# simmodule_adapter_v2_0_1_nov2023.net
KiCad netlist of a schematic drawn in EAGLE
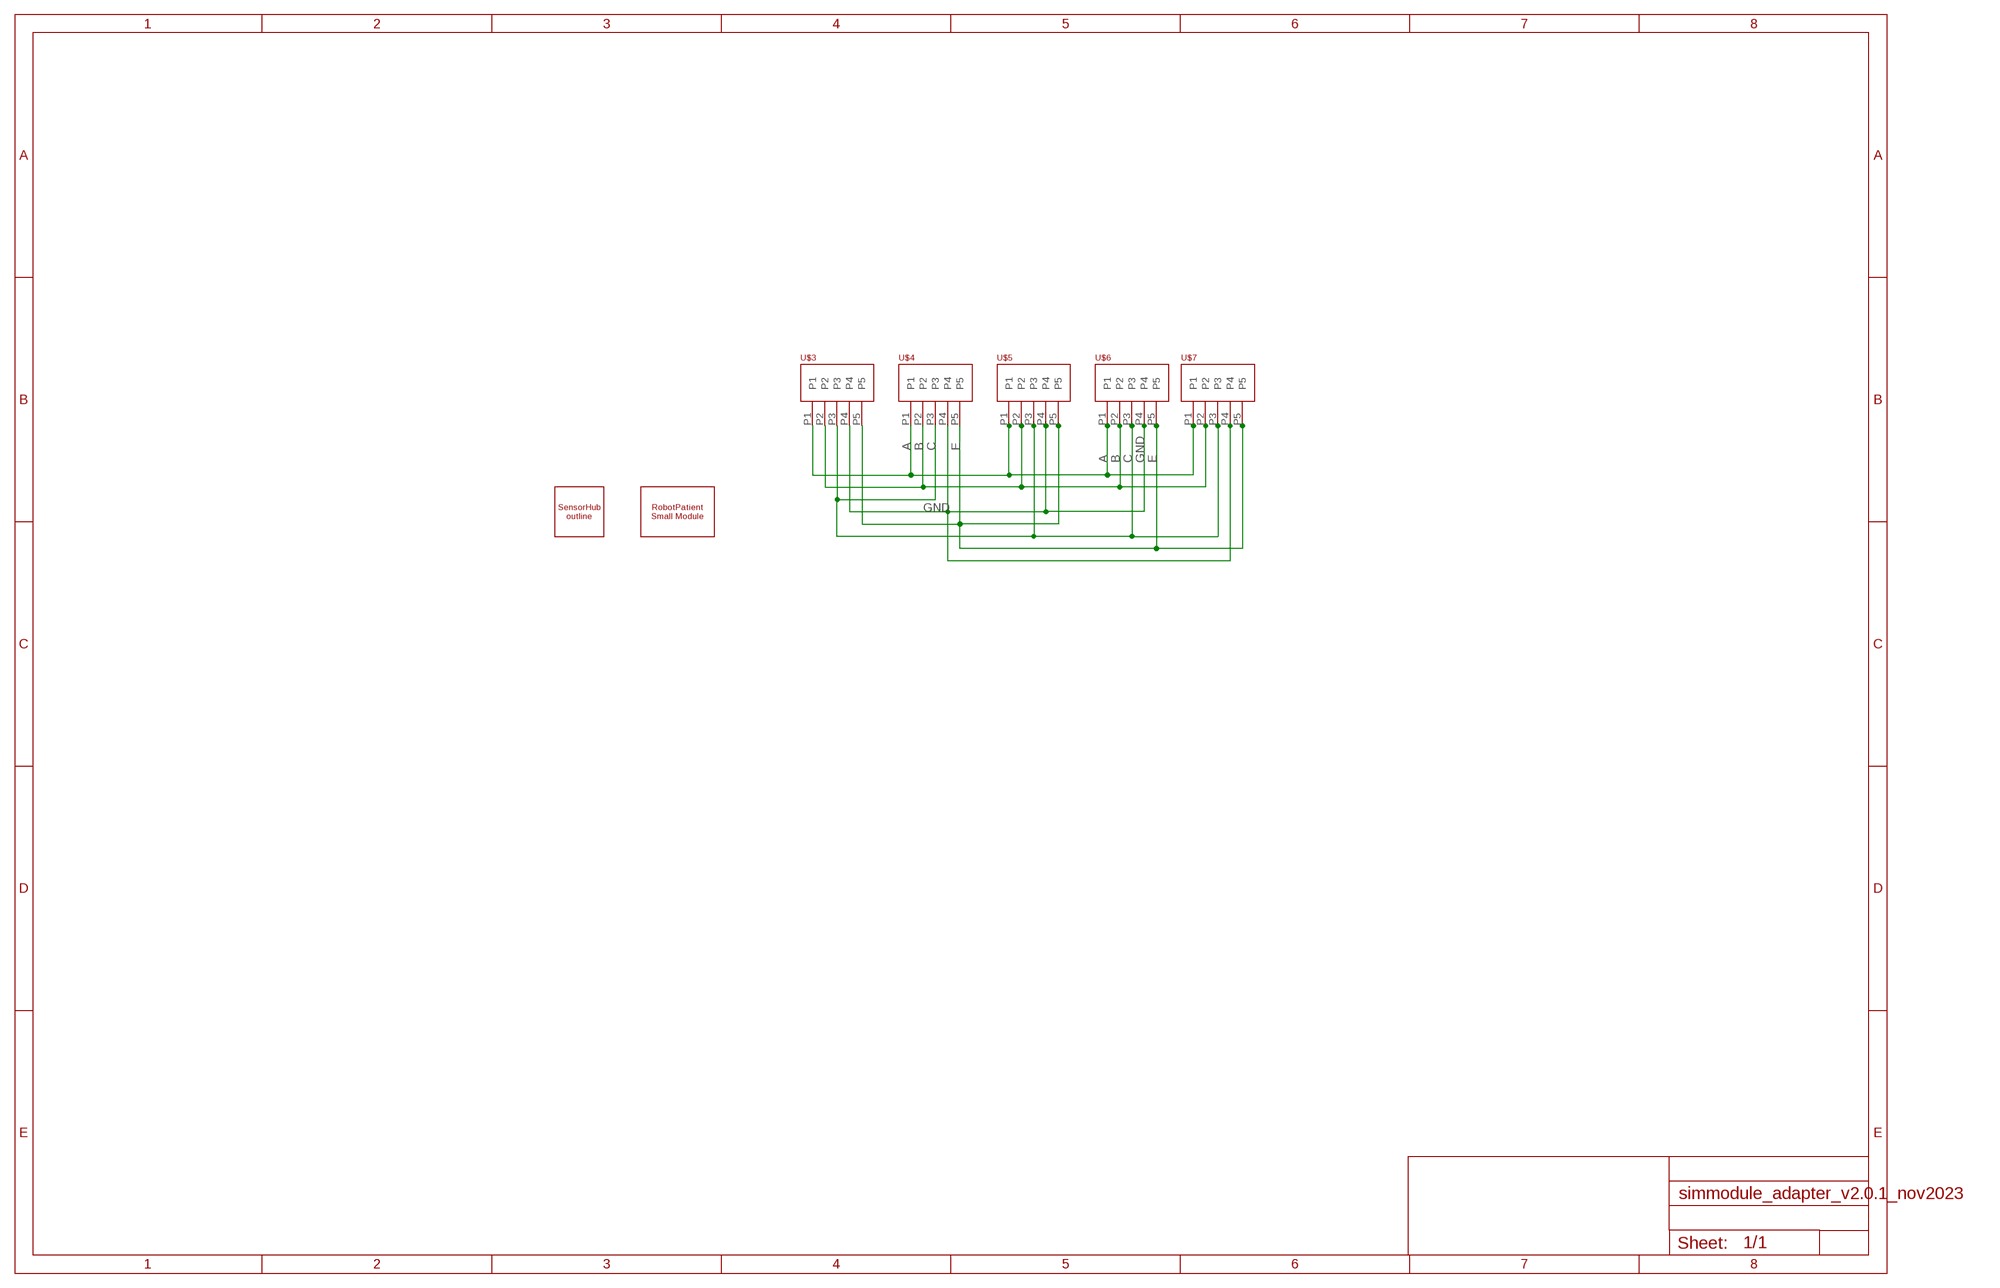
[diagram p0: schematic, sheet 1]

(export (version "E")
  (design (tool "Eeschema 10.0.6"))
  (components
    (comp (ref "U$1")
      (value "SENSORHUB_PROFILEBOARD")
      (footprint "eagle-import:SENSORHUB_OUTLINE")
      (libsource (lib "eagle-import") (part "SENSORHUB_PROFILEBOARD"))
    )
    (comp (ref "U$2")
      (value "ROBOTPATIENT_SMALL_MODULEOUTLINE")
      (footprint "eagle-import:ROBOTPATIENT_SMALL")
      (libsource (lib "eagle-import") (part "ROBOTPATIENT_SMALL_MODULEOUTLINE"))
    )
    (comp (ref "U$3")
      (value "PHOENIX_PTSM_M5_NEUTRAL")
      (footprint "eagle-import:PTSM_M5_TH_NEUTRAL")
      (libsource (lib "eagle-import") (part "PHOENIX_PTSM_M5_NEUTRAL"))
    )
    (comp (ref "U$4")
      (value "PHOENIX_PTSM_M5_NEUTRAL")
      (footprint "eagle-import:PTSM_M5_TH_NEUTRAL")
      (libsource (lib "eagle-import") (part "PHOENIX_PTSM_M5_NEUTRAL"))
    )
    (comp (ref "U$5")
      (value "PHOENIX_PTSM_M5_NEUTRAL")
      (footprint "eagle-import:PTSM_M5_TH_NEUTRAL")
      (libsource (lib "eagle-import") (part "PHOENIX_PTSM_M5_NEUTRAL"))
    )
    (comp (ref "U$6")
      (value "PHOENIX_PTSM_M5_NEUTRAL")
      (footprint "eagle-import:PTSM_M5_TH_NEUTRAL")
      (libsource (lib "eagle-import") (part "PHOENIX_PTSM_M5_NEUTRAL"))
    )
    (comp (ref "U$7")
      (value "PHOENIX_PTSM_M5_NEUTRAL")
      (footprint "eagle-import:PTSM_M5_TH_NEUTRAL")
      (libsource (lib "eagle-import") (part "PHOENIX_PTSM_M5_NEUTRAL"))
    )
  )
  (nets
    (net (code "1") (name "/A") (class "Default")
      (node (ref "U$3") (pin "P1") (pinfunction "P1_P1") (pintype "bidirectional"))
      (node (ref "U$4") (pin "P1") (pinfunction "P1_P1") (pintype "bidirectional"))
      (node (ref "U$5") (pin "P1") (pinfunction "P1_P1") (pintype "bidirectional"))
      (node (ref "U$6") (pin "P1") (pinfunction "P1_P1") (pintype "bidirectional"))
      (node (ref "U$7") (pin "P1") (pinfunction "P1_P1") (pintype "bidirectional"))
    )
    (net (code "2") (name "/B") (class "Default")
      (node (ref "U$3") (pin "P2") (pinfunction "P2_P2") (pintype "bidirectional"))
      (node (ref "U$4") (pin "P2") (pinfunction "P2_P2") (pintype "bidirectional"))
      (node (ref "U$5") (pin "P2") (pinfunction "P2_P2") (pintype "bidirectional"))
      (node (ref "U$6") (pin "P2") (pinfunction "P2_P2") (pintype "bidirectional"))
      (node (ref "U$7") (pin "P2") (pinfunction "P2_P2") (pintype "bidirectional"))
    )
    (net (code "3") (name "/C") (class "Default")
      (node (ref "U$3") (pin "P3") (pinfunction "P3_P3") (pintype "bidirectional"))
      (node (ref "U$4") (pin "P3") (pinfunction "P3_P3") (pintype "bidirectional"))
      (node (ref "U$5") (pin "P3") (pinfunction "P3_P3") (pintype "bidirectional"))
      (node (ref "U$6") (pin "P3") (pinfunction "P3_P3") (pintype "bidirectional"))
      (node (ref "U$7") (pin "P3") (pinfunction "P3_P3") (pintype "bidirectional"))
    )
    (net (code "4") (name "/E") (class "Default")
      (node (ref "U$3") (pin "P5") (pinfunction "P5_P5") (pintype "bidirectional"))
      (node (ref "U$4") (pin "P5") (pinfunction "P5_P5") (pintype "bidirectional"))
      (node (ref "U$5") (pin "P5") (pinfunction "P5_P5") (pintype "bidirectional"))
      (node (ref "U$6") (pin "P5") (pinfunction "P5_P5") (pintype "bidirectional"))
      (node (ref "U$7") (pin "P5") (pinfunction "P5_P5") (pintype "bidirectional"))
    )
    (net (code "5") (name "/GND") (class "Default")
      (node (ref "U$3") (pin "P4") (pinfunction "P4_P4") (pintype "bidirectional"))
      (node (ref "U$4") (pin "P4") (pinfunction "P4_P4") (pintype "bidirectional"))
      (node (ref "U$5") (pin "P4") (pinfunction "P4_P4") (pintype "bidirectional"))
      (node (ref "U$6") (pin "P4") (pinfunction "P4_P4") (pintype "bidirectional"))
      (node (ref "U$7") (pin "P4") (pinfunction "P4_P4") (pintype "bidirectional"))
    )
  )
)
